# LoraLCD.net
KiCad netlist of a schematic drawn in EAGLE
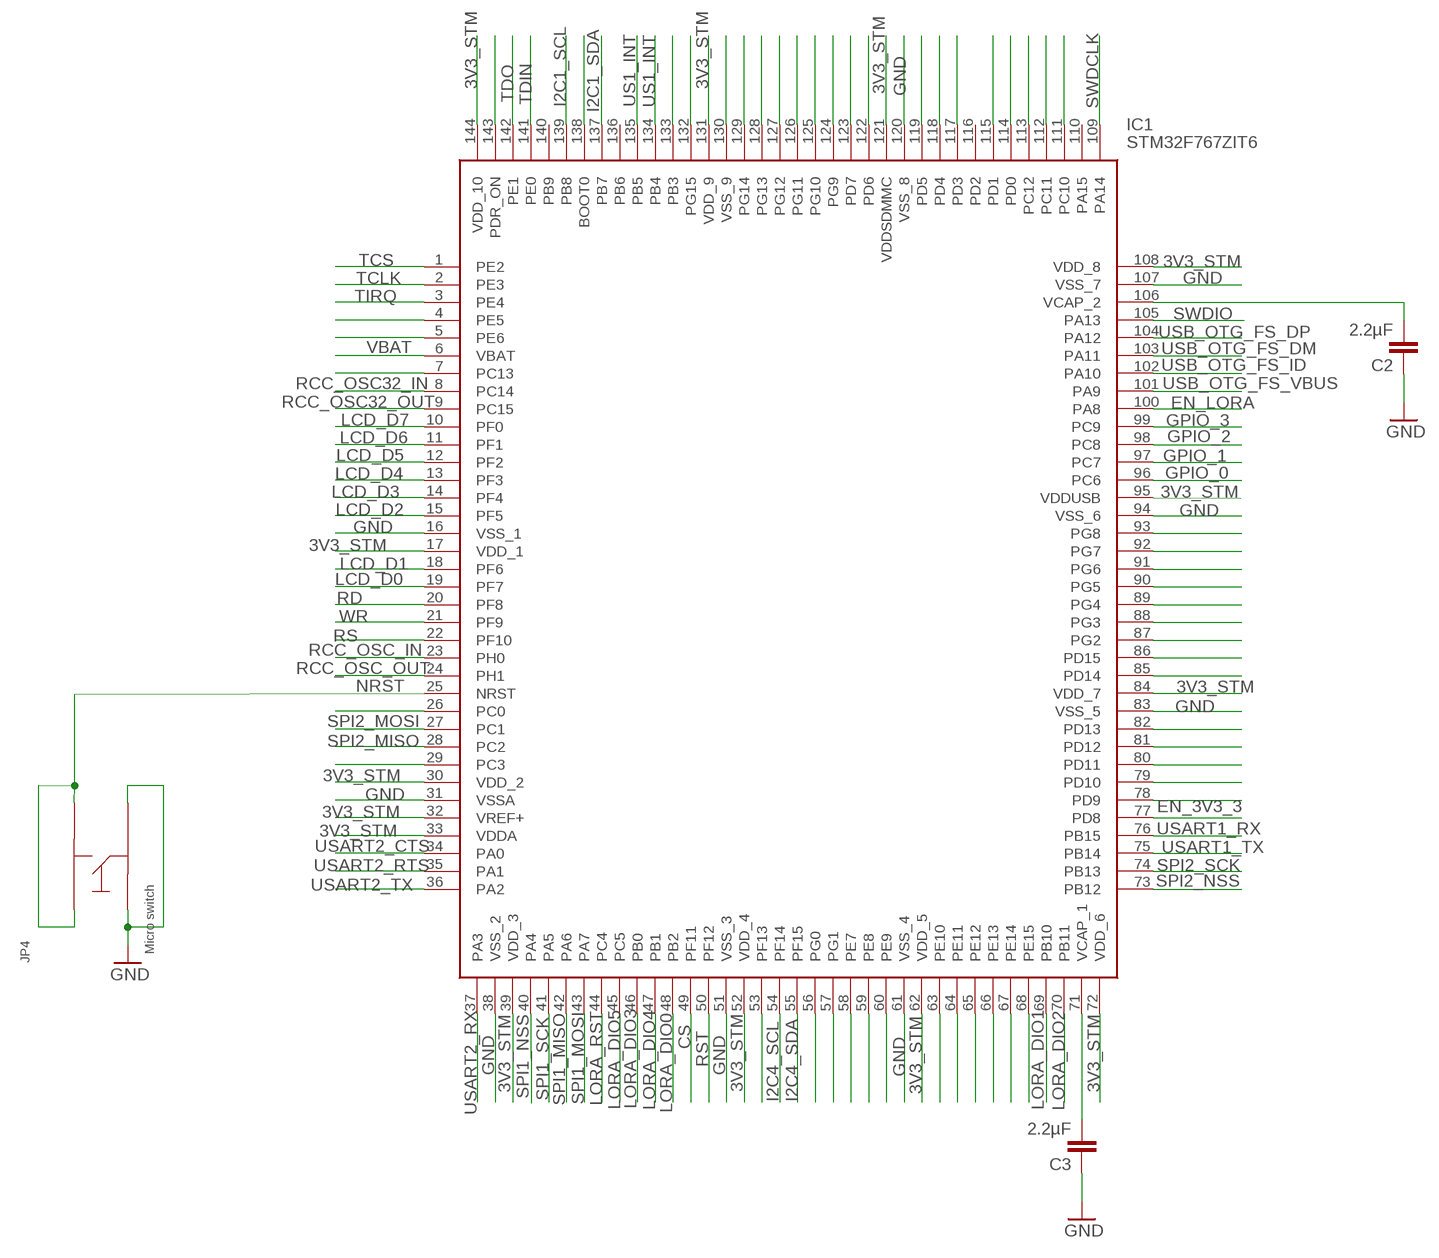
[diagram p0: schematic, sheet 1]
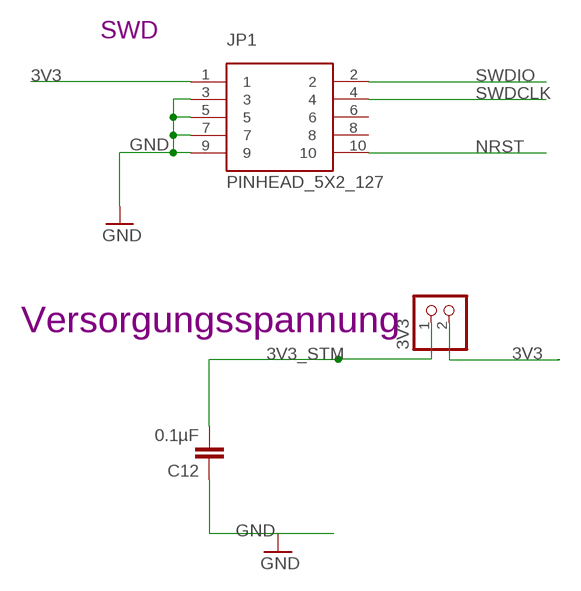
[diagram p1: schematic, sheet 2]
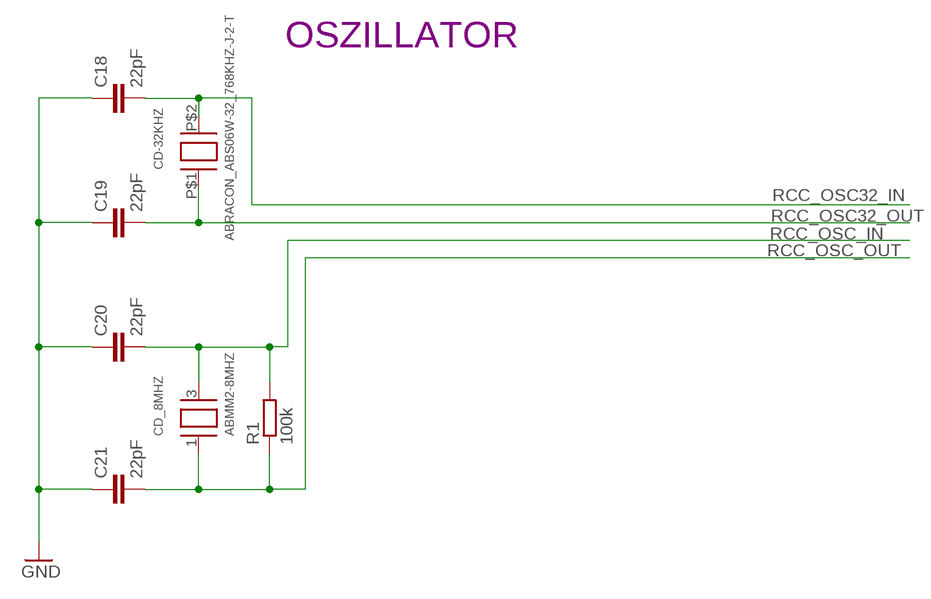
[diagram p2: schematic, sheet 3]
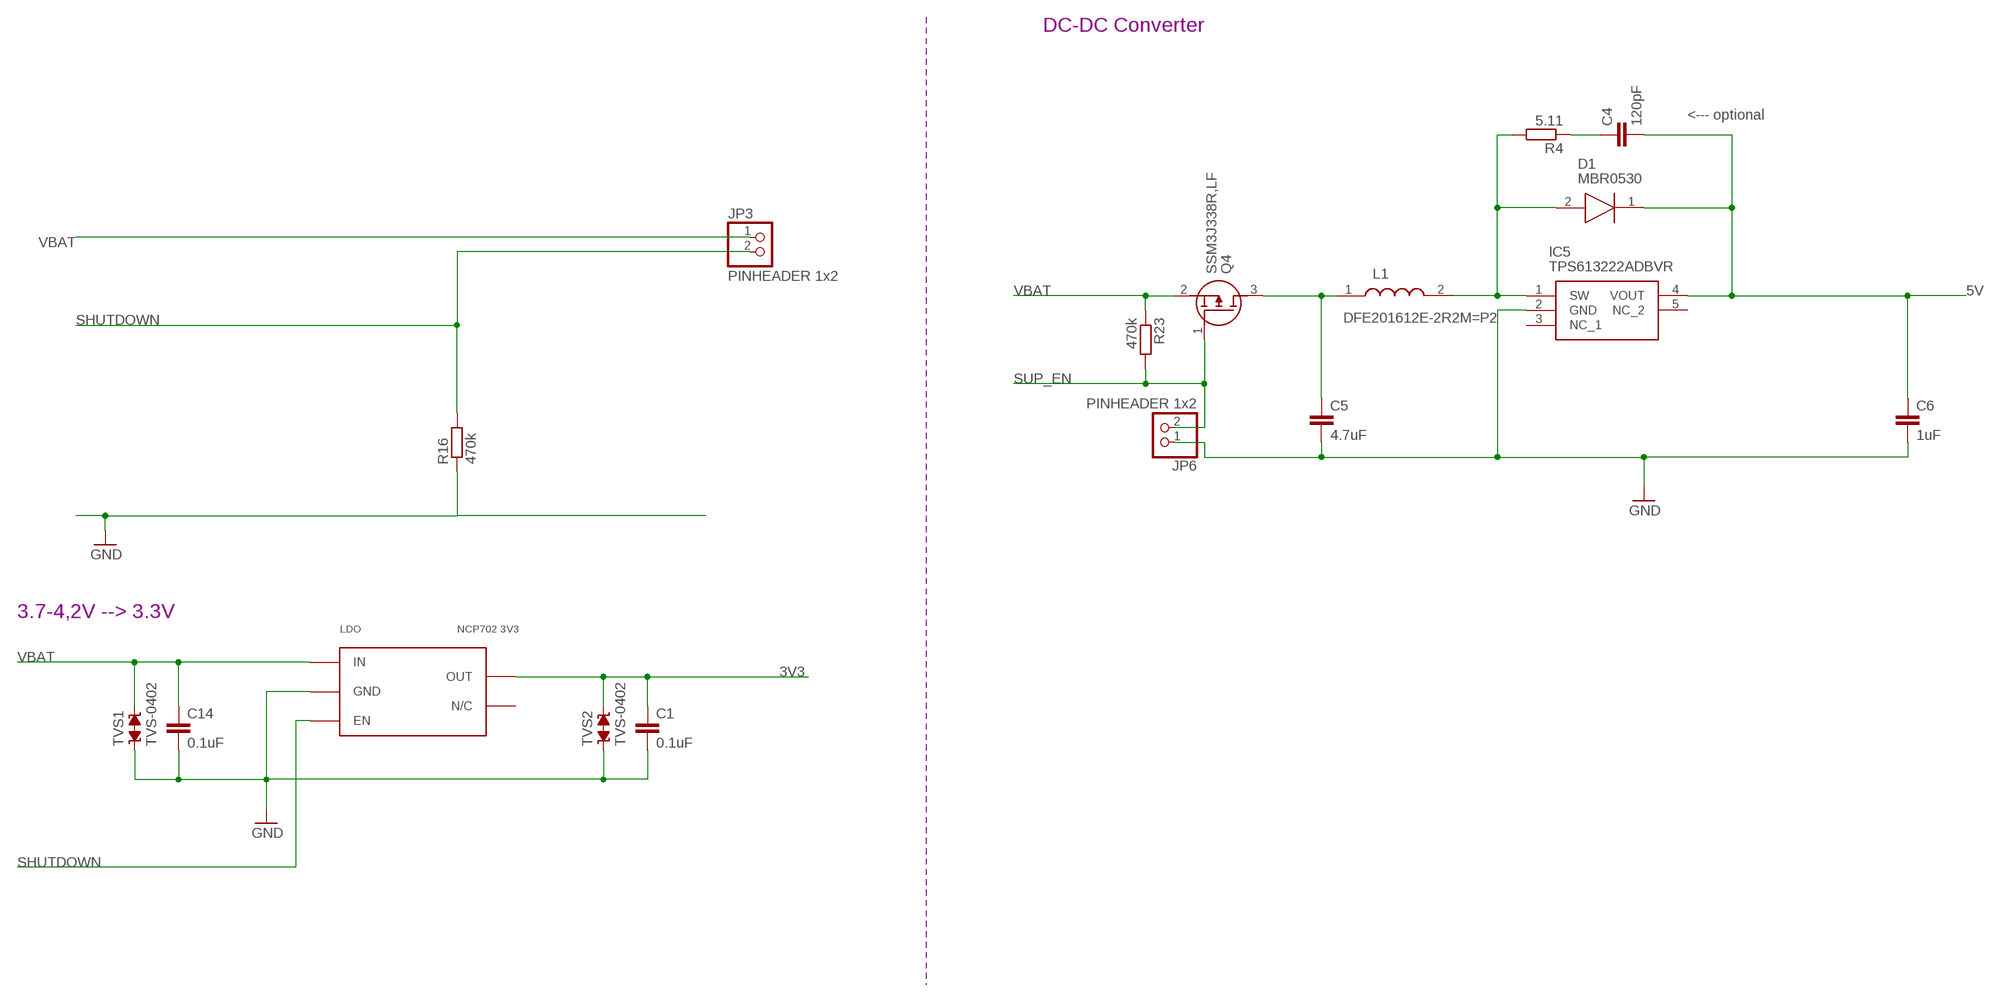
[diagram p3: schematic, sheet 4]
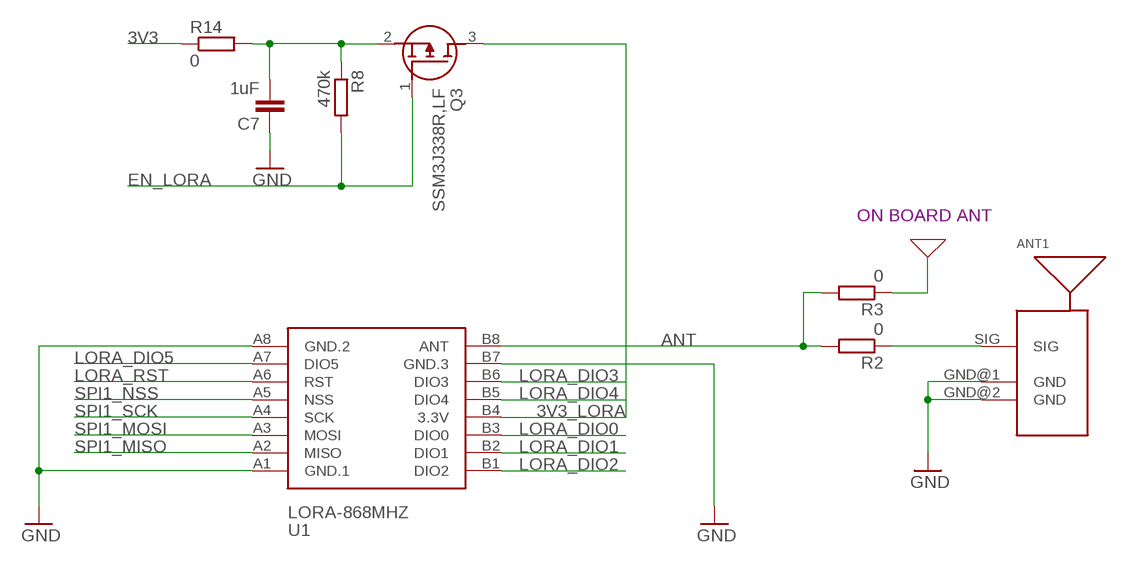
[diagram p4: schematic, sheet 5]
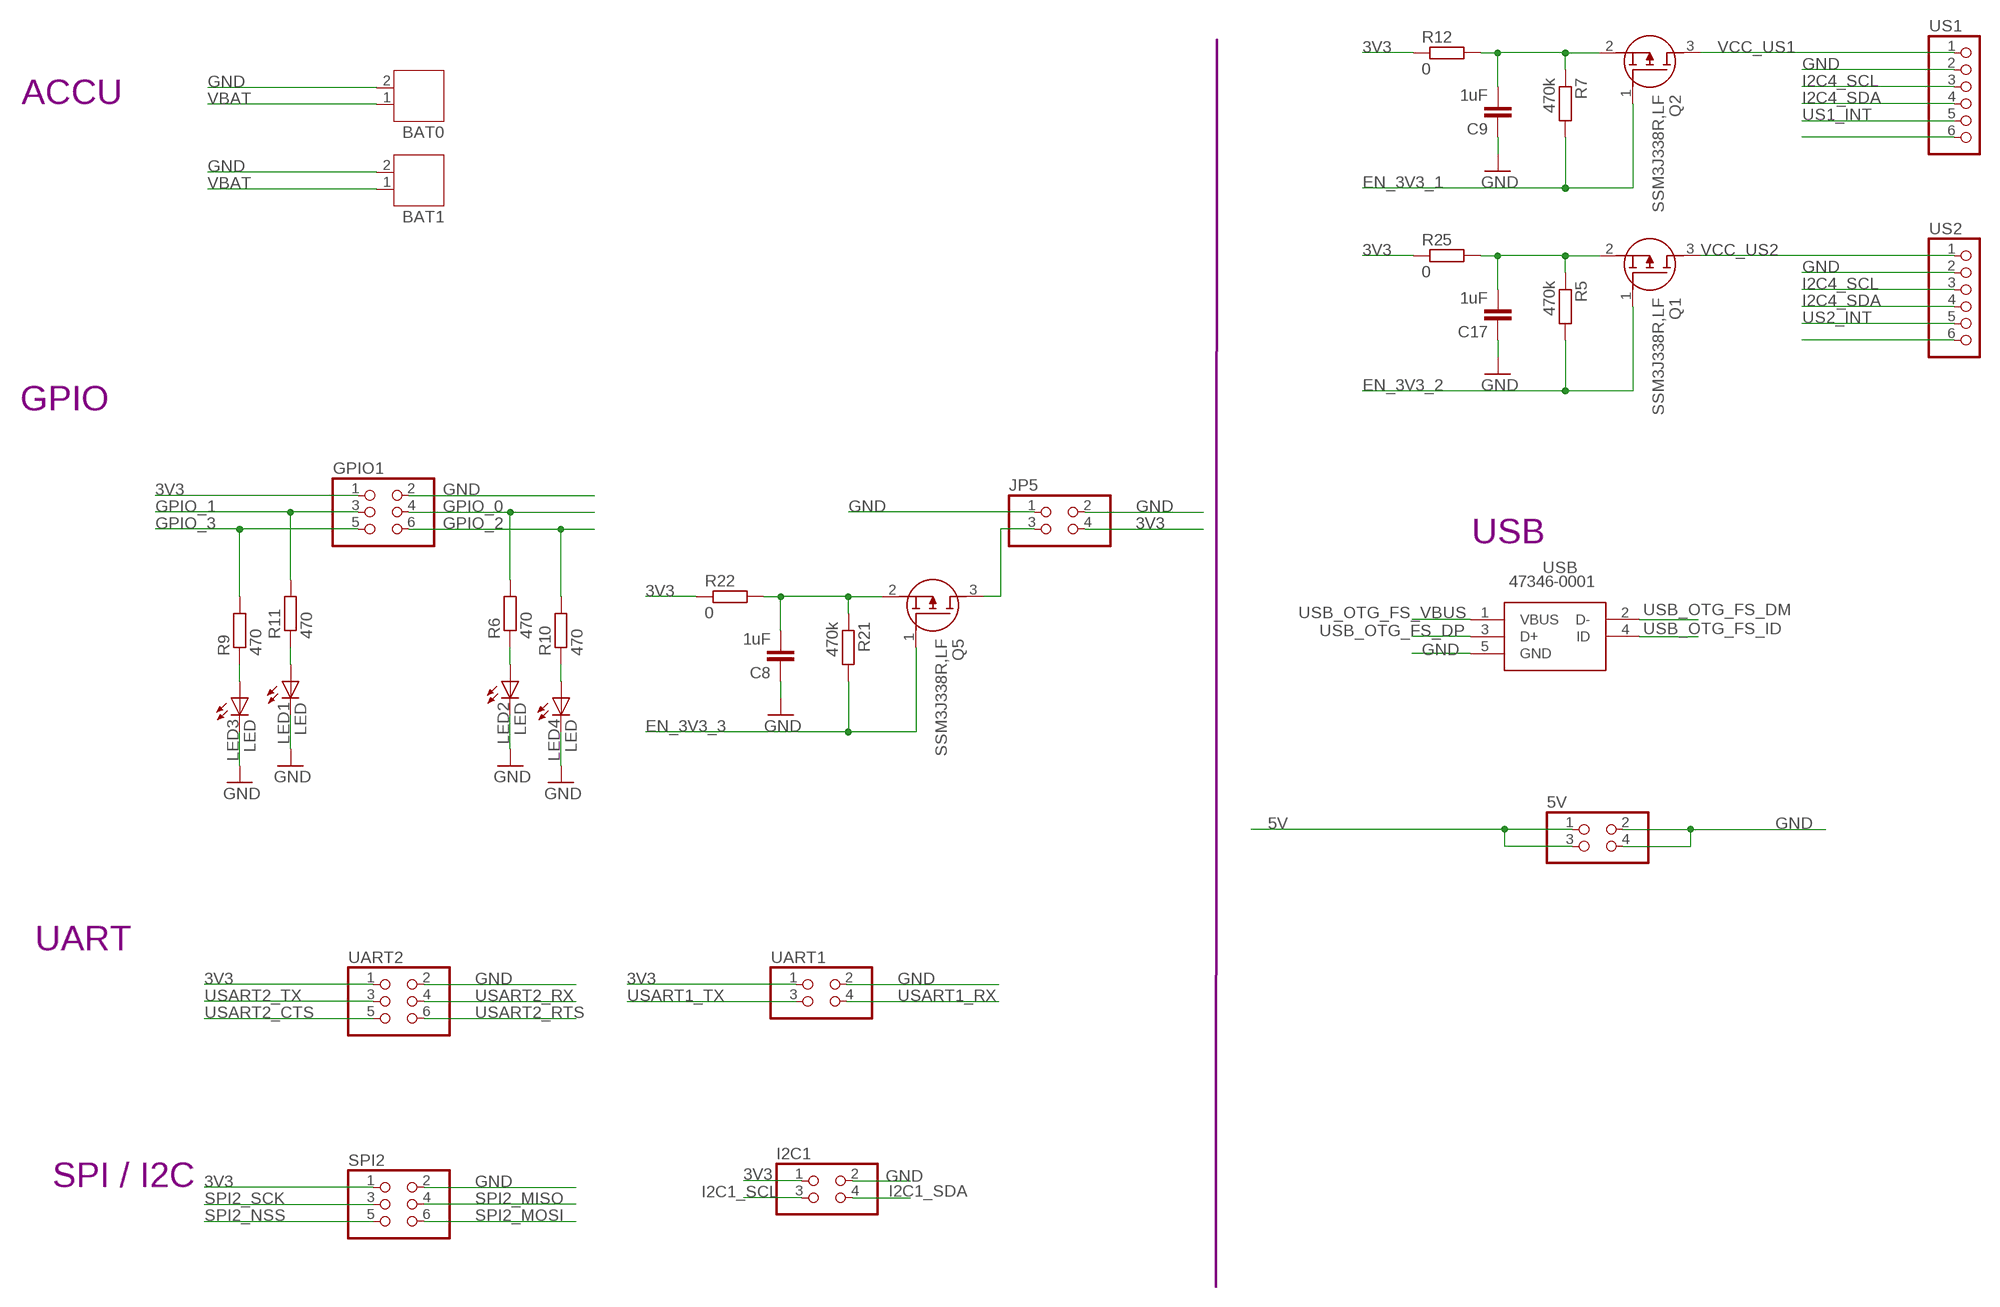
[diagram p5: schematic, sheet 6]
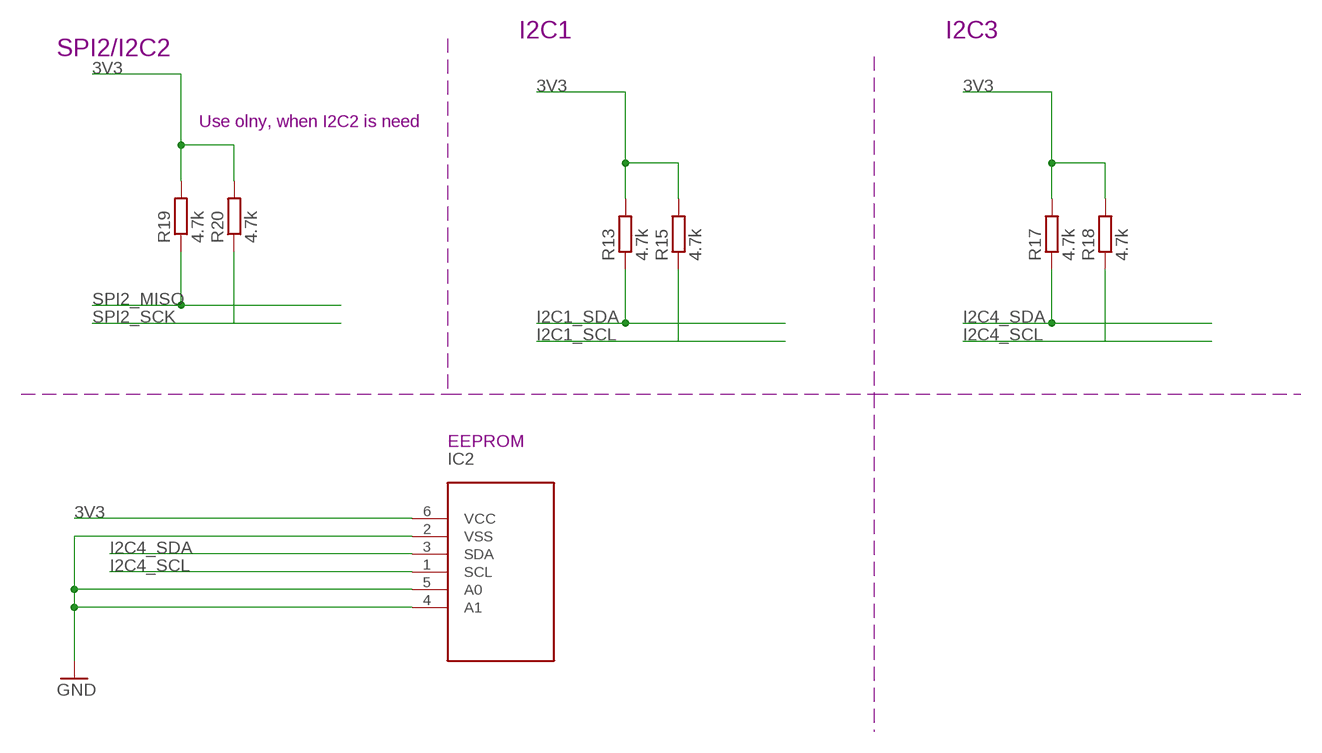
[diagram p6: schematic, sheet 7]
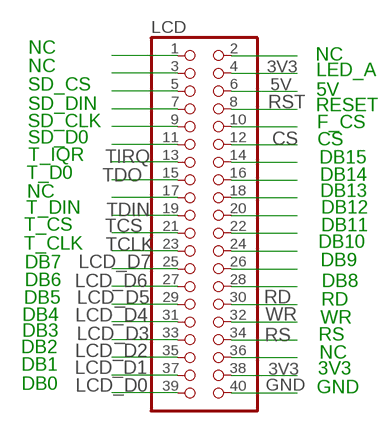
[diagram p7: schematic, sheet 8]

(export (version "E")
  (design (tool "Eeschema 10.0.6"))
  (components
    (comp (ref "C2")
      (value "2.2µF")
      (footprint "eagle-import:C0402K")
      (libsource (lib "eagle-import") (part "C-EUC0402K"))
    )
    (comp (ref "C3")
      (value "2.2µF")
      (footprint "eagle-import:C0402K")
      (libsource (lib "eagle-import") (part "C-EUC0402K"))
    )
    (comp (ref "IC1")
      (value "STM32F767ZIT6")
      (footprint "eagle-import:QFP50P2200X2200X160-144N")
      (fields (field (name "MOUSER_PART_NUMBER") "511-STM32F767ZIT6"))
      (libsource (lib "eagle-import") (part "STM32F767ZIT6"))
    )
    (comp (ref "JP4")
      (value "MICRO_SWITCH_6MM")
      (footprint "eagle-import:SKQGADE010")
      (fields
        (field (name "MPN") "SKQGABE010")
        (field (name "MF") "ALPS")
        (field (name "MPN_1") "SKQGADE010")
      )
      (libsource (lib "eagle-import") (part "MICRO_SWITCH_6MM"))
    )
    (comp (ref "IC2")
      (value "24AA025E64T-I/OT")
      (footprint "eagle-import:SOT23-6")
      (fields (field (name "MF") "Microchip Technology"))
      (libsource (lib "eagle-import") (part "24AA025E48T-I/OT"))
    )
    (comp (ref "R13")
      (value "4.7k")
      (footprint "eagle-import:C0402K")
      (libsource (lib "eagle-import") (part "R_0402WEB_0402"))
    )
    (comp (ref "R15")
      (value "4.7k")
      (footprint "eagle-import:C0402K")
      (libsource (lib "eagle-import") (part "R_0402WEB_0402"))
    )
    (comp (ref "R17")
      (value "4.7k")
      (footprint "eagle-import:C0402K")
      (libsource (lib "eagle-import") (part "R_0402WEB_0402"))
    )
    (comp (ref "R18")
      (value "4.7k")
      (footprint "eagle-import:C0402K")
      (libsource (lib "eagle-import") (part "R_0402WEB_0402"))
    )
    (comp (ref "R19")
      (value "4.7k")
      (footprint "eagle-import:C0402K")
      (libsource (lib "eagle-import") (part "R_0402WEB_0402"))
    )
    (comp (ref "R20")
      (value "4.7k")
      (footprint "eagle-import:C0402K")
      (libsource (lib "eagle-import") (part "R_0402WEB_0402"))
    )
    (comp (ref "C18")
      (value "22pF")
      (footprint "eagle-import:C0402K")
      (libsource (lib "eagle-import") (part "C-EUC0402K"))
    )
    (comp (ref "C19")
      (value "22pF")
      (footprint "eagle-import:C0402K")
      (libsource (lib "eagle-import") (part "C-EUC0402K"))
    )
    (comp (ref "C20")
      (value "22pF")
      (footprint "eagle-import:C0402K")
      (libsource (lib "eagle-import") (part "C-EUC0402K"))
    )
    (comp (ref "C21")
      (value "22pF")
      (footprint "eagle-import:C0402K")
      (libsource (lib "eagle-import") (part "C-EUC0402K"))
    )
    (comp (ref "CD-32KHZ")
      (value "ABRACON_ABS06W-32_768KHZ-J-2-T")
      (footprint "eagle-import:2MM_X_1_2MM")
      (libsource (lib "eagle-import") (part "ABRACON_ABS06W-32_768KHZ-J-2-T"))
    )
    (comp (ref "CD_8MHZ")
      (value "ABMM2-8MHZ")
      (footprint "eagle-import:CRYSTAL_ABRACON_6MM_3.6MM")
      (fields (field (name "MPN") "ABMM2-8.0000MHZ-E1-T"))
      (libsource (lib "eagle-import") (part "ABMM2-8MHZ"))
    )
    (comp (ref "R1")
      (value "100k")
      (footprint "eagle-import:C0402K")
      (libsource (lib "eagle-import") (part "R_0402WEB_0402"))
    )
    (comp (ref "ANT1")
      (value "U.FL-R-SMT-1")
      (footprint "eagle-import:UFL_HIROSE")
      (fields (field (name "MF") "HIROSE Connector") (field (name "MPN") "U.FL-R-SMT-1(10)"))
      (libsource (lib "eagle-import") (part "U.FL-R-SMT-1"))
    )
    (comp (ref "C7")
      (value "1uF")
      (footprint "eagle-import:C0402K")
      (libsource (lib "eagle-import") (part "C-EUC0402K"))
    )
    (comp (ref "Q3")
      (value "SSM3J338R,LF")
      (footprint "eagle-import:SSM3J332RLFT")
      (fields (field (name "MOUSER_PART_NUMBER") "757-SSM3J338RLF"))
      (libsource (lib "eagle-import") (part "SSM3J338R,LF"))
    )
    (comp (ref "R2")
      (value "0")
      (footprint "eagle-import:C0402K")
      (libsource (lib "eagle-import") (part "R_0402WEB_0402"))
    )
    (comp (ref "R3")
      (value "0")
      (footprint "eagle-import:C0402K")
      (libsource (lib "eagle-import") (part "R_0402WEB_0402"))
    )
    (comp (ref "R8")
      (value "470k")
      (footprint "eagle-import:R0402")
      (libsource (lib "eagle-import") (part "R-EU_R0402"))
    )
    (comp (ref "R14")
      (value "0")
      (footprint "eagle-import:R0402")
      (libsource (lib "eagle-import") (part "R-EU_R0402"))
    )
    (comp (ref "U1")
      (value "LORA-868MHZ")
      (footprint "eagle-import:WIRELESS-LORA-RFM95W#SMD")
      (libsource (lib "eagle-import") (part "WIRELESS-LORA-RFM95W#SMD"))
    )
    (comp (ref "3V3")
      (value "PINHD-1X2")
      (footprint "eagle-import:1X02")
      (libsource (lib "eagle-import") (part "PINHD-1X2"))
    )
    (comp (ref "C12")
      (value "0.1µF")
      (footprint "eagle-import:C0402K")
      (libsource (lib "eagle-import") (part "C-EUC0402K"))
    )
    (comp (ref "JP1")
      (value "PINHEAD_5X2_127")
      (footprint "eagle-import:PINHEAD_2X5_127")
      (fields (field (name "MPN") "3221-10-0100-00"))
      (libsource (lib "eagle-import") (part "PINHEAD_5X2_127"))
    )
    (comp (ref "C1")
      (value "0.1uF")
      (footprint "eagle-import:C0402K")
      (fields (field (name "MF") "NOVA") (field (name "MPN") "CCC-23"))
      (libsource (lib "eagle-import") (part "C-EUC0402K"))
    )
    (comp (ref "C4")
      (value "120pF")
      (footprint "eagle-import:C0402K")
      (fields (field (name "MPN") "GRM1555C1H121JA01D"))
      (libsource (lib "eagle-import") (part "C-EUC0402K"))
    )
    (comp (ref "C5")
      (value "4.7uF")
      (footprint "eagle-import:C0603K")
      (fields (field (name "MF") "Taiyo Yuden") (field (name "MPN") "JMK107BB7475KA-T "))
      (libsource (lib "eagle-import") (part "C-EUC0603K"))
    )
    (comp (ref "C6")
      (value "1uF")
      (footprint "eagle-import:C0603K")
      (libsource (lib "eagle-import") (part "C-EUC0603K"))
    )
    (comp (ref "C14")
      (value "0.1uF")
      (footprint "eagle-import:C0402K")
      (libsource (lib "eagle-import") (part "C-EUC0402K"))
    )
    (comp (ref "D1")
      (value "MBR0530")
      (footprint "eagle-import:SOD3716X135N")
      (fields (field (name "MOUSER_PART_NUMBER") "512-MBR0530"))
      (libsource (lib "eagle-import") (part "MBR0530"))
    )
    (comp (ref "IC5")
      (value "TPS613222ADBVR")
      (footprint "eagle-import:SOT95P280X145-5N")
      (fields (field (name "MOUSER_PART_NUMBER") "595-TPS613222ADBVR"))
      (libsource (lib "eagle-import") (part "TPS613222ADBVR"))
    )
    (comp (ref "JP3")
      (value "PINHEADER 1x2")
      (footprint "eagle-import:1X02")
      (libsource (lib "eagle-import") (part "PINHD-1X2"))
    )
    (comp (ref "JP6")
      (value "PINHEADER 1x2")
      (footprint "eagle-import:1X02")
      (libsource (lib "eagle-import") (part "PINHD-1X2"))
    )
    (comp (ref "L1")
      (value "DFE201612E-2R2M=P2")
      (footprint "eagle-import:INDC2016X120N")
      (fields (field (name "MOUSER_PART_NUMBER") "81-DFE201612E-2R2MP2"))
      (libsource (lib "eagle-import") (part "DFE201612E-2R2M=P2"))
    )
    (comp (ref "LDO")
      (value "NCP702 3V3")
      (footprint "eagle-import:SOT563")
      (fields
        (field (name "MOUSER_PART_NUMBER") "863-NCP702SN33T1G")
        (field (name "MF") "ON Semiconductor")
        (field (name "MPN") "NCP702SN33T1G")
      )
      (libsource (lib "eagle-import") (part "NCP702"))
    )
    (comp (ref "Q4")
      (value "SSM3J338R,LF")
      (footprint "eagle-import:SSM3J332RLFT")
      (fields (field (name "MOUSER_PART_NUMBER") "757-SSM3J338RLF"))
      (libsource (lib "eagle-import") (part "SSM3J338R,LF"))
    )
    (comp (ref "R4")
      (value "5.11")
      (footprint "eagle-import:R0402")
      (fields (field (name "MF") "Yageo") (field (name "MPN") "RC0402FR-132M2L "))
      (libsource (lib "eagle-import") (part "R-EU_R0402"))
    )
    (comp (ref "R16")
      (value "470k")
      (footprint "eagle-import:R0402")
      (libsource (lib "eagle-import") (part "R-EU_R0402"))
    )
    (comp (ref "R23")
      (value "470k")
      (footprint "eagle-import:R0402")
      (libsource (lib "eagle-import") (part "R-EU_R0402"))
    )
    (comp (ref "TVS1")
      (value "TVS-0402")
      (footprint "eagle-import:TVS0402")
      (fields
        (field (name "MPN") "GG0402050R3C2P")
        (field (name "MF") "Littelfuse")
        (field (name "MPN_1") "PESD0402-140 ")
      )
      (libsource (lib "eagle-import") (part "TVS-0402"))
    )
    (comp (ref "TVS2")
      (value "TVS-0402")
      (footprint "eagle-import:TVS0402")
      (fields
        (field (name "MPN") "GG0402050R3C2P")
        (field (name "MF") "Littelfuse")
        (field (name "MPN_1") "PESD0402-140 ")
      )
      (libsource (lib "eagle-import") (part "TVS-0402"))
    )
    (comp (ref "LCD")
      (value "PINHD-2X20")
      (footprint "eagle-import:2X20")
      (libsource (lib "eagle-import") (part "PINHD-2X20"))
    )
    (comp (ref "5V")
      (value "PINHD-2X2")
      (footprint "eagle-import:2X02")
      (libsource (lib "eagle-import") (part "PINHD-2X2"))
    )
    (comp (ref "BAT0")
      (value "JST-PH2")
      (footprint "eagle-import:JST-PH2")
      (fields (field (name "MF") "JST Sales America Inc.") (field (name "MPN") "B2B-PH-K-S"))
      (libsource (lib "eagle-import") (part "JST-PH2"))
    )
    (comp (ref "BAT1")
      (value "JST-PH2")
      (footprint "eagle-import:JST-PH2")
      (fields (field (name "MF") "JST Sales America Inc.") (field (name "MPN") "B2B-PH-K-S"))
      (libsource (lib "eagle-import") (part "JST-PH2"))
    )
    (comp (ref "C8")
      (value "1uF")
      (footprint "eagle-import:C0402K")
      (libsource (lib "eagle-import") (part "C-EUC0402K"))
    )
    (comp (ref "C9")
      (value "1uF")
      (footprint "eagle-import:C0402K")
      (libsource (lib "eagle-import") (part "C-EUC0402K"))
    )
    (comp (ref "C17")
      (value "1uF")
      (footprint "eagle-import:C0402K")
      (libsource (lib "eagle-import") (part "C-EUC0402K"))
    )
    (comp (ref "GPIO1")
      (value "PINHD-2X3")
      (footprint "eagle-import:2X03")
      (libsource (lib "eagle-import") (part "PINHD-2X3"))
    )
    (comp (ref "I2C1")
      (value "PINHD-2X2")
      (footprint "eagle-import:2X02")
      (libsource (lib "eagle-import") (part "PINHD-2X2"))
    )
    (comp (ref "JP5")
      (value "PINHD-2X2")
      (footprint "eagle-import:2X02")
      (libsource (lib "eagle-import") (part "PINHD-2X2"))
    )
    (comp (ref "LED1")
      (value "LED")
      (footprint "eagle-import:0603_AK")
      (fields (field (name "MPN") "LB Q39G-L2OO-35-1"))
      (libsource (lib "eagle-import") (part "LED"))
    )
    (comp (ref "LED2")
      (value "LED")
      (footprint "eagle-import:0603_AK")
      (fields (field (name "MPN") "LB Q39G-L2OO-35-1"))
      (libsource (lib "eagle-import") (part "LED"))
    )
    (comp (ref "LED3")
      (value "LED")
      (footprint "eagle-import:0603_AK")
      (fields (field (name "MPN") "LB Q39G-L2OO-35-1"))
      (libsource (lib "eagle-import") (part "LED"))
    )
    (comp (ref "LED4")
      (value "LED")
      (footprint "eagle-import:0603_AK")
      (fields (field (name "MPN") "LB Q39G-L2OO-35-1"))
      (libsource (lib "eagle-import") (part "LED"))
    )
    (comp (ref "Q1")
      (value "SSM3J338R,LF")
      (footprint "eagle-import:SSM3J332RLFT")
      (fields (field (name "MOUSER_PART_NUMBER") "757-SSM3J338RLF"))
      (libsource (lib "eagle-import") (part "SSM3J338R,LF"))
    )
    (comp (ref "Q2")
      (value "SSM3J338R,LF")
      (footprint "eagle-import:SSM3J332RLFT")
      (fields (field (name "MOUSER_PART_NUMBER") "757-SSM3J338RLF"))
      (libsource (lib "eagle-import") (part "SSM3J338R,LF"))
    )
    (comp (ref "Q5")
      (value "SSM3J338R,LF")
      (footprint "eagle-import:SSM3J332RLFT")
      (fields (field (name "MOUSER_PART_NUMBER") "757-SSM3J338RLF"))
      (libsource (lib "eagle-import") (part "SSM3J338R,LF"))
    )
    (comp (ref "R5")
      (value "470k")
      (footprint "eagle-import:R0402")
      (libsource (lib "eagle-import") (part "R-EU_R0402"))
    )
    (comp (ref "R6")
      (value "470")
      (footprint "eagle-import:R0402")
      (libsource (lib "eagle-import") (part "R-EU_R0402"))
    )
    (comp (ref "R7")
      (value "470k")
      (footprint "eagle-import:R0402")
      (libsource (lib "eagle-import") (part "R-EU_R0402"))
    )
    (comp (ref "R9")
      (value "470")
      (footprint "eagle-import:R0402")
      (libsource (lib "eagle-import") (part "R-EU_R0402"))
    )
    (comp (ref "R10")
      (value "470")
      (footprint "eagle-import:R0402")
      (libsource (lib "eagle-import") (part "R-EU_R0402"))
    )
    (comp (ref "R11")
      (value "470")
      (footprint "eagle-import:R0402")
      (libsource (lib "eagle-import") (part "R-EU_R0402"))
    )
    (comp (ref "R12")
      (value "0")
      (footprint "eagle-import:R0402")
      (libsource (lib "eagle-import") (part "R-EU_R0402"))
    )
    (comp (ref "R21")
      (value "470k")
      (footprint "eagle-import:R0402")
      (libsource (lib "eagle-import") (part "R-EU_R0402"))
    )
    (comp (ref "R22")
      (value "0")
      (footprint "eagle-import:R0402")
      (libsource (lib "eagle-import") (part "R-EU_R0402"))
    )
    (comp (ref "R25")
      (value "0")
      (footprint "eagle-import:R0402")
      (libsource (lib "eagle-import") (part "R-EU_R0402"))
    )
    (comp (ref "SPI2")
      (value "PINHD-2X3")
      (footprint "eagle-import:2X03")
      (libsource (lib "eagle-import") (part "PINHD-2X3"))
    )
    (comp (ref "UART1")
      (value "PINHD-2X2")
      (footprint "eagle-import:2X02")
      (libsource (lib "eagle-import") (part "PINHD-2X2"))
    )
    (comp (ref "UART2")
      (value "PINHD-2X3")
      (footprint "eagle-import:2X03")
      (libsource (lib "eagle-import") (part "PINHD-2X3"))
    )
    (comp (ref "US1")
      (value "PINHD-1X6")
      (footprint "eagle-import:1X06")
      (libsource (lib "eagle-import") (part "PINHD-1X6"))
    )
    (comp (ref "US2")
      (value "PINHD-1X6")
      (footprint "eagle-import:1X06")
      (libsource (lib "eagle-import") (part "PINHD-1X6"))
    )
    (comp (ref "USB")
      (value "47346-0001")
      (footprint "eagle-import:47346-0001")
      (libsource (lib "eagle-import") (part "47346-0001"))
    )
  )
  (nets
    (net (code "1") (name "3V3") (class "Default")
      (node (ref "3V3") (pin "2") (pinfunction "2_2") (pintype "passive"))
      (node (ref "C1") (pin "1") (pinfunction "1_1") (pintype "passive"))
      (node (ref "GPIO1") (pin "1") (pinfunction "1_1") (pintype "passive"))
      (node (ref "I2C1") (pin "1") (pinfunction "1_1") (pintype "passive"))
      (node (ref "IC2") (pin "6") (pinfunction "VCC_6") (pintype "bidirectional"))
      (node (ref "JP1") (pin "1") (pinfunction "1_1") (pintype "bidirectional"))
      (node (ref "JP5") (pin "4") (pinfunction "4_4") (pintype "passive"))
      (node (ref "LCD") (pin "38") (pinfunction "38_38") (pintype "passive"))
      (node (ref "LCD") (pin "4") (pinfunction "4_4") (pintype "passive"))
      (node (ref "LDO") (pin "P$5") (pinfunction "OUT_P$5") (pintype "bidirectional"))
      (node (ref "R12") (pin "1") (pinfunction "1_1") (pintype "passive"))
      (node (ref "R13") (pin "2") (pinfunction "2_2") (pintype "passive"))
      (node (ref "R14") (pin "1") (pinfunction "1_1") (pintype "passive"))
      (node (ref "R15") (pin "2") (pinfunction "2_2") (pintype "passive"))
      (node (ref "R17") (pin "2") (pinfunction "2_2") (pintype "passive"))
      (node (ref "R18") (pin "2") (pinfunction "2_2") (pintype "passive"))
      (node (ref "R19") (pin "2") (pinfunction "2_2") (pintype "passive"))
      (node (ref "R20") (pin "2") (pinfunction "2_2") (pintype "passive"))
      (node (ref "R22") (pin "1") (pinfunction "1_1") (pintype "passive"))
      (node (ref "R25") (pin "1") (pinfunction "1_1") (pintype "passive"))
      (node (ref "SPI2") (pin "1") (pinfunction "1_1") (pintype "passive"))
      (node (ref "TVS2") (pin "2") (pinfunction "2_2") (pintype "passive"))
      (node (ref "UART1") (pin "1") (pinfunction "1_1") (pintype "passive"))
      (node (ref "UART2") (pin "1") (pinfunction "1_1") (pintype "passive"))
    )
    (net (code "2") (name "3V3_LORA") (class "Default")
      (node (ref "Q3") (pin "3") (pinfunction "D_3") (pintype "bidirectional"))
      (node (ref "U1") (pin "B4") (pinfunction "3.3V_B4") (pintype "power_in"))
    )
    (net (code "3") (name "3V3_STM") (class "Default")
      (node (ref "3V3") (pin "1") (pinfunction "1_1") (pintype "passive"))
      (node (ref "C12") (pin "2") (pinfunction "2_2") (pintype "passive"))
      (node (ref "IC1") (pin "108") (pinfunction "VDD_8_108") (pintype "bidirectional"))
      (node (ref "IC1") (pin "121") (pinfunction "VDDSDMMC_121") (pintype "bidirectional"))
      (node (ref "IC1") (pin "131") (pinfunction "VDD_9_131") (pintype "bidirectional"))
      (node (ref "IC1") (pin "144") (pinfunction "VDD_10_144") (pintype "bidirectional"))
      (node (ref "IC1") (pin "17") (pinfunction "VDD_1_17") (pintype "bidirectional"))
      (node (ref "IC1") (pin "30") (pinfunction "VDD_2_30") (pintype "bidirectional"))
      (node (ref "IC1") (pin "32") (pinfunction "VREF+_32") (pintype "bidirectional"))
      (node (ref "IC1") (pin "33") (pinfunction "VDDA_33") (pintype "bidirectional"))
      (node (ref "IC1") (pin "39") (pinfunction "VDD_3_39") (pintype "bidirectional"))
      (node (ref "IC1") (pin "52") (pinfunction "VDD_4_52") (pintype "bidirectional"))
      (node (ref "IC1") (pin "62") (pinfunction "VDD_5_62") (pintype "bidirectional"))
      (node (ref "IC1") (pin "72") (pinfunction "VDD_6_72") (pintype "bidirectional"))
      (node (ref "IC1") (pin "84") (pinfunction "VDD_7_84") (pintype "bidirectional"))
      (node (ref "IC1") (pin "95") (pinfunction "VDDUSB_95") (pintype "bidirectional"))
    )
    (net (code "4") (name "5V") (class "Default")
      (node (ref "5V") (pin "1") (pinfunction "1_1") (pintype "passive"))
      (node (ref "5V") (pin "3") (pinfunction "3_3") (pintype "passive"))
      (node (ref "C4") (pin "2") (pinfunction "2_2") (pintype "passive"))
      (node (ref "C6") (pin "1") (pinfunction "1_1") (pintype "passive"))
      (node (ref "D1") (pin "1") (pinfunction "K_1") (pintype "bidirectional"))
      (node (ref "IC5") (pin "4") (pinfunction "VOUT_4") (pintype "bidirectional"))
      (node (ref "LCD") (pin "6") (pinfunction "6_6") (pintype "passive"))
    )
    (net (code "5") (name "ANT") (class "Default")
      (node (ref "R2") (pin "2") (pinfunction "2_2") (pintype "passive"))
      (node (ref "R3") (pin "2") (pinfunction "2_2") (pintype "passive"))
      (node (ref "U1") (pin "B8") (pinfunction "ANT_B8") (pintype "passive"))
    )
    (net (code "6") (name "CS") (class "Default")
      (node (ref "IC1") (pin "49") (pinfunction "PF11_49") (pintype "bidirectional"))
      (node (ref "LCD") (pin "12") (pinfunction "12_12") (pintype "passive"))
    )
    (net (code "7") (name "EN_3V3_1") (class "Default")
      (node (ref "Q2") (pin "1") (pinfunction "G_1") (pintype "bidirectional"))
      (node (ref "R7") (pin "2") (pinfunction "2_2") (pintype "passive"))
    )
    (net (code "8") (name "EN_3V3_2") (class "Default")
      (node (ref "Q1") (pin "1") (pinfunction "G_1") (pintype "bidirectional"))
      (node (ref "R5") (pin "2") (pinfunction "2_2") (pintype "passive"))
    )
    (net (code "9") (name "EN_3V3_3") (class "Default")
      (node (ref "IC1") (pin "77") (pinfunction "PD8_77") (pintype "bidirectional"))
      (node (ref "Q5") (pin "1") (pinfunction "G_1") (pintype "bidirectional"))
      (node (ref "R21") (pin "2") (pinfunction "2_2") (pintype "passive"))
    )
    (net (code "10") (name "EN_LORA") (class "Default")
      (node (ref "IC1") (pin "100") (pinfunction "PA8_100") (pintype "bidirectional"))
      (node (ref "Q3") (pin "1") (pinfunction "G_1") (pintype "bidirectional"))
      (node (ref "R8") (pin "2") (pinfunction "2_2") (pintype "passive"))
    )
    (net (code "11") (name "GND") (class "Default")
      (node (ref "5V") (pin "2") (pinfunction "2_2") (pintype "passive"))
      (node (ref "5V") (pin "4") (pinfunction "4_4") (pintype "passive"))
      (node (ref "ANT1") (pin "GND@1") (pinfunction "GND_GND@1") (pintype "bidirectional"))
      (node (ref "ANT1") (pin "GND@2") (pinfunction "GND_GND@2") (pintype "bidirectional"))
      (node (ref "BAT0") (pin "2") (pinfunction "2_2") (pintype "passive"))
      (node (ref "BAT1") (pin "2") (pinfunction "2_2") (pintype "passive"))
      (node (ref "C1") (pin "2") (pinfunction "2_2") (pintype "passive"))
      (node (ref "C12") (pin "1") (pinfunction "1_1") (pintype "passive"))
      (node (ref "C14") (pin "2") (pinfunction "2_2") (pintype "passive"))
      (node (ref "C17") (pin "1") (pinfunction "1_1") (pintype "passive"))
      (node (ref "C18") (pin "1") (pinfunction "1_1") (pintype "passive"))
      (node (ref "C19") (pin "1") (pinfunction "1_1") (pintype "passive"))
      (node (ref "C2") (pin "1") (pinfunction "1_1") (pintype "passive"))
      (node (ref "C20") (pin "1") (pinfunction "1_1") (pintype "passive"))
      (node (ref "C21") (pin "1") (pinfunction "1_1") (pintype "passive"))
      (node (ref "C3") (pin "1") (pinfunction "1_1") (pintype "passive"))
      (node (ref "C5") (pin "2") (pinfunction "2_2") (pintype "passive"))
      (node (ref "C6") (pin "2") (pinfunction "2_2") (pintype "passive"))
      (node (ref "C7") (pin "1") (pinfunction "1_1") (pintype "passive"))
      (node (ref "C8") (pin "1") (pinfunction "1_1") (pintype "passive"))
      (node (ref "C9") (pin "1") (pinfunction "1_1") (pintype "passive"))
      (node (ref "GPIO1") (pin "2") (pinfunction "2_2") (pintype "passive"))
      (node (ref "I2C1") (pin "2") (pinfunction "2_2") (pintype "passive"))
      (node (ref "IC1") (pin "107") (pinfunction "VSS_7_107") (pintype "bidirectional"))
      (node (ref "IC1") (pin "120") (pinfunction "VSS_8_120") (pintype "bidirectional"))
      (node (ref "IC1") (pin "16") (pinfunction "VSS_1_16") (pintype "bidirectional"))
      (node (ref "IC1") (pin "31") (pinfunction "VSSA_31") (pintype "bidirectional"))
      (node (ref "IC1") (pin "38") (pinfunction "VSS_2_38") (pintype "bidirectional"))
      (node (ref "IC1") (pin "51") (pinfunction "VSS_3_51") (pintype "bidirectional"))
      (node (ref "IC1") (pin "61") (pinfunction "VSS_4_61") (pintype "bidirectional"))
      (node (ref "IC1") (pin "83") (pinfunction "VSS_5_83") (pintype "bidirectional"))
      (node (ref "IC1") (pin "94") (pinfunction "VSS_6_94") (pintype "bidirectional"))
      (node (ref "IC2") (pin "2") (pinfunction "VSS_2") (pintype "bidirectional"))
      (node (ref "IC2") (pin "4") (pinfunction "A1_4") (pintype "bidirectional"))
      (node (ref "IC2") (pin "5") (pinfunction "A0_5") (pintype "bidirectional"))
      (node (ref "IC5") (pin "2") (pinfunction "GND_2") (pintype "bidirectional"))
      (node (ref "JP1") (pin "3") (pinfunction "3_3") (pintype "bidirectional"))
      (node (ref "JP1") (pin "5") (pinfunction "5_5") (pintype "bidirectional"))
      (node (ref "JP1") (pin "7") (pinfunction "7_7") (pintype "bidirectional"))
      (node (ref "JP1") (pin "9") (pinfunction "9_9") (pintype "bidirectional"))
      (node (ref "JP4") (pin "P$3") (pinfunction "P$3_P$3") (pintype "bidirectional"))
      (node (ref "JP4") (pin "P$4") (pinfunction "P$4_P$4") (pintype "bidirectional"))
      (node (ref "JP5") (pin "1") (pinfunction "1_1") (pintype "passive"))
      (node (ref "JP5") (pin "2") (pinfunction "2_2") (pintype "passive"))
      (node (ref "JP6") (pin "1") (pinfunction "1_1") (pintype "passive"))
      (node (ref "LCD") (pin "40") (pinfunction "40_40") (pintype "passive"))
      (node (ref "LDO") (pin "P$2") (pinfunction "GND_P$2") (pintype "bidirectional"))
      (node (ref "LED1") (pin "K") (pinfunction "C_K") (pintype "passive"))
      (node (ref "LED2") (pin "K") (pinfunction "C_K") (pintype "passive"))
      (node (ref "LED3") (pin "K") (pinfunction "C_K") (pintype "passive"))
      (node (ref "LED4") (pin "K") (pinfunction "C_K") (pintype "passive"))
      (node (ref "R16") (pin "1") (pinfunction "1_1") (pintype "passive"))
      (node (ref "SPI2") (pin "2") (pinfunction "2_2") (pintype "passive"))
      (node (ref "TVS1") (pin "1") (pinfunction "1_1") (pintype "passive"))
      (node (ref "TVS2") (pin "1") (pinfunction "1_1") (pintype "passive"))
      (node (ref "U1") (pin "A1") (pinfunction "GND.1_A1") (pintype "power_in"))
      (node (ref "U1") (pin "A8") (pinfunction "GND.2_A8") (pintype "power_in"))
      (node (ref "U1") (pin "B7") (pinfunction "GND.3_B7") (pintype "power_in"))
      (node (ref "UART1") (pin "2") (pinfunction "2_2") (pintype "passive"))
      (node (ref "UART2") (pin "2") (pinfunction "2_2") (pintype "passive"))
      (node (ref "US1") (pin "2") (pinfunction "2_2") (pintype "passive"))
      (node (ref "US2") (pin "2") (pinfunction "2_2") (pintype "passive"))
      (node (ref "USB") (pin "5") (pinfunction "GND_5") (pintype "bidirectional"))
    )
    (net (code "12") (name "GPIO_0") (class "Default")
      (node (ref "GPIO1") (pin "4") (pinfunction "4_4") (pintype "passive"))
      (node (ref "IC1") (pin "96") (pinfunction "PC6_96") (pintype "bidirectional"))
      (node (ref "R6") (pin "2") (pinfunction "2_2") (pintype "passive"))
    )
    (net (code "13") (name "GPIO_1") (class "Default")
      (node (ref "GPIO1") (pin "3") (pinfunction "3_3") (pintype "passive"))
      (node (ref "IC1") (pin "97") (pinfunction "PC7_97") (pintype "bidirectional"))
      (node (ref "R11") (pin "2") (pinfunction "2_2") (pintype "passive"))
    )
    (net (code "14") (name "GPIO_2") (class "Default")
      (node (ref "GPIO1") (pin "6") (pinfunction "6_6") (pintype "passive"))
      (node (ref "IC1") (pin "98") (pinfunction "PC8_98") (pintype "bidirectional"))
      (node (ref "R10") (pin "2") (pinfunction "2_2") (pintype "passive"))
    )
    (net (code "15") (name "GPIO_3") (class "Default")
      (node (ref "GPIO1") (pin "5") (pinfunction "5_5") (pintype "passive"))
      (node (ref "IC1") (pin "99") (pinfunction "PC9_99") (pintype "bidirectional"))
      (node (ref "R9") (pin "2") (pinfunction "2_2") (pintype "passive"))
    )
    (net (code "16") (name "I2C1_SCL") (class "Default")
      (node (ref "I2C1") (pin "3") (pinfunction "3_3") (pintype "passive"))
      (node (ref "IC1") (pin "139") (pinfunction "PB8_139") (pintype "bidirectional"))
      (node (ref "R15") (pin "1") (pinfunction "1_1") (pintype "passive"))
    )
    (net (code "17") (name "I2C1_SDA") (class "Default")
      (node (ref "I2C1") (pin "4") (pinfunction "4_4") (pintype "passive"))
      (node (ref "IC1") (pin "137") (pinfunction "PB7_137") (pintype "bidirectional"))
      (node (ref "R13") (pin "1") (pinfunction "1_1") (pintype "passive"))
    )
    (net (code "18") (name "I2C4_SCL") (class "Default")
      (node (ref "IC1") (pin "54") (pinfunction "PF14_54") (pintype "bidirectional"))
      (node (ref "IC2") (pin "1") (pinfunction "SCL_1") (pintype "bidirectional"))
      (node (ref "R18") (pin "1") (pinfunction "1_1") (pintype "passive"))
      (node (ref "US1") (pin "3") (pinfunction "3_3") (pintype "passive"))
      (node (ref "US2") (pin "3") (pinfunction "3_3") (pintype "passive"))
    )
    (net (code "19") (name "I2C4_SDA") (class "Default")
      (node (ref "IC1") (pin "55") (pinfunction "PF15_55") (pintype "bidirectional"))
      (node (ref "IC2") (pin "3") (pinfunction "SDA_3") (pintype "bidirectional"))
      (node (ref "R17") (pin "1") (pinfunction "1_1") (pintype "passive"))
      (node (ref "US1") (pin "4") (pinfunction "4_4") (pintype "passive"))
      (node (ref "US2") (pin "4") (pinfunction "4_4") (pintype "passive"))
    )
    (net (code "20") (name "LCD_D0") (class "Default")
      (node (ref "IC1") (pin "19") (pinfunction "PF7_19") (pintype "bidirectional"))
      (node (ref "LCD") (pin "39") (pinfunction "39_39") (pintype "passive"))
    )
    (net (code "21") (name "LCD_D1") (class "Default")
      (node (ref "IC1") (pin "18") (pinfunction "PF6_18") (pintype "bidirectional"))
      (node (ref "LCD") (pin "37") (pinfunction "37_37") (pintype "passive"))
    )
    (net (code "22") (name "LCD_D2") (class "Default")
      (node (ref "IC1") (pin "15") (pinfunction "PF5_15") (pintype "bidirectional"))
      (node (ref "LCD") (pin "35") (pinfunction "35_35") (pintype "passive"))
    )
    (net (code "23") (name "LCD_D3") (class "Default")
      (node (ref "IC1") (pin "14") (pinfunction "PF4_14") (pintype "bidirectional"))
      (node (ref "LCD") (pin "33") (pinfunction "33_33") (pintype "passive"))
    )
    (net (code "24") (name "LCD_D4") (class "Default")
      (node (ref "IC1") (pin "13") (pinfunction "PF3_13") (pintype "bidirectional"))
      (node (ref "LCD") (pin "31") (pinfunction "31_31") (pintype "passive"))
    )
    (net (code "25") (name "LCD_D5") (class "Default")
      (node (ref "IC1") (pin "12") (pinfunction "PF2_12") (pintype "bidirectional"))
      (node (ref "LCD") (pin "29") (pinfunction "29_29") (pintype "passive"))
    )
    (net (code "26") (name "LCD_D6") (class "Default")
      (node (ref "IC1") (pin "11") (pinfunction "PF1_11") (pintype "bidirectional"))
      (node (ref "LCD") (pin "27") (pinfunction "27_27") (pintype "passive"))
    )
    (net (code "27") (name "LCD_D7") (class "Default")
      (node (ref "IC1") (pin "10") (pinfunction "PF0_10") (pintype "bidirectional"))
      (node (ref "LCD") (pin "25") (pinfunction "25_25") (pintype "passive"))
    )
    (net (code "28") (name "LORA_DIO0") (class "Default")
      (node (ref "IC1") (pin "48") (pinfunction "PB2_48") (pintype "bidirectional"))
      (node (ref "U1") (pin "B3") (pinfunction "DIO0_B3") (pintype "bidirectional"))
    )
    (net (code "29") (name "LORA_DIO1") (class "Default")
      (node (ref "IC1") (pin "69") (pinfunction "PB10_69") (pintype "bidirectional"))
      (node (ref "U1") (pin "B2") (pinfunction "DIO1_B2") (pintype "bidirectional"))
    )
    (net (code "30") (name "LORA_DIO2") (class "Default")
      (node (ref "IC1") (pin "70") (pinfunction "PB11_70") (pintype "bidirectional"))
      (node (ref "U1") (pin "B1") (pinfunction "DIO2_B1") (pintype "bidirectional"))
    )
    (net (code "31") (name "LORA_DIO3") (class "Default")
      (node (ref "IC1") (pin "46") (pinfunction "PB0_46") (pintype "bidirectional"))
      (node (ref "U1") (pin "B6") (pinfunction "DIO3_B6") (pintype "bidirectional"))
    )
    (net (code "32") (name "LORA_DIO4") (class "Default")
      (node (ref "IC1") (pin "47") (pinfunction "PB1_47") (pintype "bidirectional"))
      (node (ref "U1") (pin "B5") (pinfunction "DIO4_B5") (pintype "bidirectional"))
    )
    (net (code "33") (name "LORA_DIO5") (class "Default")
      (node (ref "IC1") (pin "45") (pinfunction "PC5_45") (pintype "bidirectional"))
      (node (ref "U1") (pin "A7") (pinfunction "DIO5_A7") (pintype "bidirectional"))
    )
    (net (code "34") (name "LORA_RST") (class "Default")
      (node (ref "IC1") (pin "44") (pinfunction "PC4_44") (pintype "bidirectional"))
      (node (ref "U1") (pin "A6") (pinfunction "RST_A6") (pintype "bidirectional"))
    )
    (net (code "35") (name "NRST") (class "Default")
      (node (ref "IC1") (pin "25") (pinfunction "NRST_25") (pintype "bidirectional"))
      (node (ref "JP1") (pin "10") (pinfunction "10_10") (pintype "bidirectional"))
      (node (ref "JP4") (pin "P$1") (pinfunction "P$1_P$1") (pintype "bidirectional"))
      (node (ref "JP4") (pin "P$2") (pinfunction "P$2_P$2") (pintype "bidirectional"))
    )
    (net (code "36") (name "Net-(ANT1-PadSIG)") (class "Default")
      (node (ref "ANT1") (pin "SIG") (pinfunction "SIG_SIG") (pintype "bidirectional"))
      (node (ref "R2") (pin "1") (pinfunction "1_1") (pintype "passive"))
    )
    (net (code "37") (name "Net-(C4-Pad1)") (class "Default")
      (node (ref "C4") (pin "1") (pinfunction "1_1") (pintype "passive"))
      (node (ref "R4") (pin "1") (pinfunction "1_1") (pintype "passive"))
    )
    (net (code "38") (name "Net-(D1-A)") (class "Default")
      (node (ref "D1") (pin "2") (pinfunction "A_2") (pintype "bidirectional"))
      (node (ref "IC5") (pin "1") (pinfunction "SW_1") (pintype "bidirectional"))
      (node (ref "L1") (pin "2") (pinfunction "2_2") (pintype "bidirectional"))
      (node (ref "R4") (pin "2") (pinfunction "2_2") (pintype "passive"))
    )
    (net (code "39") (name "Net-(IC1-VCAP_1)") (class "Default")
      (node (ref "C3") (pin "2") (pinfunction "2_2") (pintype "passive"))
      (node (ref "IC1") (pin "71") (pinfunction "VCAP_1_71") (pintype "bidirectional"))
    )
    (net (code "40") (name "Net-(IC1-VCAP_2)") (class "Default")
      (node (ref "C2") (pin "2") (pinfunction "2_2") (pintype "passive"))
      (node (ref "IC1") (pin "106") (pinfunction "VCAP_2_106") (pintype "bidirectional"))
    )
    (net (code "41") (name "Net-(LED1-PadA)") (class "Default")
      (node (ref "LED1") (pin "A") (pinfunction "A_A") (pintype "passive"))
      (node (ref "R11") (pin "1") (pinfunction "1_1") (pintype "passive"))
    )
    (net (code "42") (name "Net-(LED2-PadA)") (class "Default")
      (node (ref "LED2") (pin "A") (pinfunction "A_A") (pintype "passive"))
      (node (ref "R6") (pin "1") (pinfunction "1_1") (pintype "passive"))
    )
    (net (code "43") (name "Net-(LED3-PadA)") (class "Default")
      (node (ref "LED3") (pin "A") (pinfunction "A_A") (pintype "passive"))
      (node (ref "R9") (pin "1") (pinfunction "1_1") (pintype "passive"))
    )
    (net (code "44") (name "Net-(LED4-PadA)") (class "Default")
      (node (ref "LED4") (pin "A") (pinfunction "A_A") (pintype "passive"))
      (node (ref "R10") (pin "1") (pinfunction "1_1") (pintype "passive"))
    )
    (net (code "45") (name "Net-(Q1-S)") (class "Default")
      (node (ref "C17") (pin "2") (pinfunction "2_2") (pintype "passive"))
      (node (ref "Q1") (pin "2") (pinfunction "S_2") (pintype "bidirectional"))
      (node (ref "R25") (pin "2") (pinfunction "2_2") (pintype "passive"))
      (node (ref "R5") (pin "1") (pinfunction "1_1") (pintype "passive"))
    )
    (net (code "46") (name "Net-(Q2-S)") (class "Default")
      (node (ref "C9") (pin "2") (pinfunction "2_2") (pintype "passive"))
      (node (ref "Q2") (pin "2") (pinfunction "S_2") (pintype "bidirectional"))
      (node (ref "R12") (pin "2") (pinfunction "2_2") (pintype "passive"))
      (node (ref "R7") (pin "1") (pinfunction "1_1") (pintype "passive"))
    )
    (net (code "47") (name "Net-(Q3-S)") (class "Default")
      (node (ref "C7") (pin "2") (pinfunction "2_2") (pintype "passive"))
      (node (ref "Q3") (pin "2") (pinfunction "S_2") (pintype "bidirectional"))
      (node (ref "R14") (pin "2") (pinfunction "2_2") (pintype "passive"))
      (node (ref "R8") (pin "1") (pinfunction "1_1") (pintype "passive"))
    )
    (net (code "48") (name "Net-(Q4-D)") (class "Default")
      (node (ref "C5") (pin "1") (pinfunction "1_1") (pintype "passive"))
      (node (ref "L1") (pin "1") (pinfunction "1_1") (pintype "bidirectional"))
      (node (ref "Q4") (pin "3") (pinfunction "D_3") (pintype "bidirectional"))
    )
    (net (code "49") (name "Net-(Q5-D)") (class "Default")
      (node (ref "JP5") (pin "3") (pinfunction "3_3") (pintype "passive"))
      (node (ref "Q5") (pin "3") (pinfunction "D_3") (pintype "bidirectional"))
    )
    (net (code "50") (name "Net-(Q5-S)") (class "Default")
      (node (ref "C8") (pin "2") (pinfunction "2_2") (pintype "passive"))
      (node (ref "Q5") (pin "2") (pinfunction "S_2") (pintype "bidirectional"))
      (node (ref "R21") (pin "1") (pinfunction "1_1") (pintype "passive"))
      (node (ref "R22") (pin "2") (pinfunction "2_2") (pintype "passive"))
    )
    (net (code "51") (name "RCC_OSC32_IN") (class "Default")
      (node (ref "C18") (pin "2") (pinfunction "2_2") (pintype "passive"))
      (node (ref "CD-32KHZ") (pin "P$2") (pinfunction "C1_P$2") (pintype "bidirectional"))
      (node (ref "IC1") (pin "8") (pinfunction "PC14_8") (pintype "bidirectional"))
    )
    (net (code "52") (name "RCC_OSC32_OUT") (class "Default")
      (node (ref "C19") (pin "2") (pinfunction "2_2") (pintype "passive"))
      (node (ref "CD-32KHZ") (pin "P$1") (pinfunction "C0_P$1") (pintype "bidirectional"))
      (node (ref "IC1") (pin "9") (pinfunction "PC15_9") (pintype "bidirectional"))
    )
    (net (code "53") (name "RCC_OSC_IN") (class "Default")
      (node (ref "C20") (pin "2") (pinfunction "2_2") (pintype "passive"))
      (node (ref "CD_8MHZ") (pin "3") (pinfunction "C1_3") (pintype "bidirectional"))
      (node (ref "IC1") (pin "23") (pinfunction "PH0_23") (pintype "bidirectional"))
      (node (ref "R1") (pin "2") (pinfunction "2_2") (pintype "passive"))
    )
    (net (code "54") (name "RCC_OSC_OUT") (class "Default")
      (node (ref "C21") (pin "2") (pinfunction "2_2") (pintype "passive"))
      (node (ref "CD_8MHZ") (pin "1") (pinfunction "C0_1") (pintype "bidirectional"))
      (node (ref "IC1") (pin "24") (pinfunction "PH1_24") (pintype "bidirectional"))
      (node (ref "R1") (pin "1") (pinfunction "1_1") (pintype "passive"))
    )
    (net (code "55") (name "RD") (class "Default")
      (node (ref "IC1") (pin "20") (pinfunction "PF8_20") (pintype "bidirectional"))
      (node (ref "LCD") (pin "30") (pinfunction "30_30") (pintype "passive"))
    )
    (net (code "56") (name "RS") (class "Default")
      (node (ref "IC1") (pin "22") (pinfunction "PF10_22") (pintype "bidirectional"))
      (node (ref "LCD") (pin "34") (pinfunction "34_34") (pintype "passive"))
    )
    (net (code "57") (name "RST") (class "Default")
      (node (ref "IC1") (pin "50") (pinfunction "PF12_50") (pintype "bidirectional"))
      (node (ref "LCD") (pin "8") (pinfunction "8_8") (pintype "passive"))
    )
    (net (code "58") (name "SHUTDOWN") (class "Default")
      (node (ref "JP3") (pin "2") (pinfunction "2_2") (pintype "passive"))
      (node (ref "LDO") (pin "P$3") (pinfunction "EN_P$3") (pintype "bidirectional"))
      (node (ref "R16") (pin "2") (pinfunction "2_2") (pintype "passive"))
    )
    (net (code "59") (name "SPI1_MISO") (class "Default")
      (node (ref "IC1") (pin "42") (pinfunction "PA6_42") (pintype "bidirectional"))
      (node (ref "U1") (pin "A2") (pinfunction "MISO_A2") (pintype "bidirectional"))
    )
    (net (code "60") (name "SPI1_MOSI") (class "Default")
      (node (ref "IC1") (pin "43") (pinfunction "PA7_43") (pintype "bidirectional"))
      (node (ref "U1") (pin "A3") (pinfunction "MOSI_A3") (pintype "bidirectional"))
    )
    (net (code "61") (name "SPI1_NSS") (class "Default")
      (node (ref "IC1") (pin "40") (pinfunction "PA4_40") (pintype "bidirectional"))
      (node (ref "U1") (pin "A5") (pinfunction "NSS_A5") (pintype "bidirectional"))
    )
    (net (code "62") (name "SPI1_SCK") (class "Default")
      (node (ref "IC1") (pin "41") (pinfunction "PA5_41") (pintype "bidirectional"))
      (node (ref "U1") (pin "A4") (pinfunction "SCK_A4") (pintype "bidirectional"))
    )
    (net (code "63") (name "SPI2_MISO") (class "Default")
      (node (ref "IC1") (pin "28") (pinfunction "PC2_28") (pintype "bidirectional"))
      (node (ref "R19") (pin "1") (pinfunction "1_1") (pintype "passive"))
      (node (ref "SPI2") (pin "4") (pinfunction "4_4") (pintype "passive"))
    )
    (net (code "64") (name "SPI2_MOSI") (class "Default")
      (node (ref "IC1") (pin "27") (pinfunction "PC1_27") (pintype "bidirectional"))
      (node (ref "SPI2") (pin "6") (pinfunction "6_6") (pintype "passive"))
    )
    (net (code "65") (name "SPI2_NSS") (class "Default")
      (node (ref "IC1") (pin "73") (pinfunction "PB12_73") (pintype "bidirectional"))
      (node (ref "SPI2") (pin "5") (pinfunction "5_5") (pintype "passive"))
    )
    (net (code "66") (name "SPI2_SCK") (class "Default")
      (node (ref "IC1") (pin "74") (pinfunction "PB13_74") (pintype "bidirectional"))
      (node (ref "R20") (pin "1") (pinfunction "1_1") (pintype "passive"))
      (node (ref "SPI2") (pin "3") (pinfunction "3_3") (pintype "passive"))
    )
    (net (code "67") (name "SUP_EN") (class "Default")
      (node (ref "JP6") (pin "2") (pinfunction "2_2") (pintype "passive"))
      (node (ref "Q4") (pin "1") (pinfunction "G_1") (pintype "bidirectional"))
      (node (ref "R23") (pin "2") (pinfunction "2_2") (pintype "passive"))
    )
    (net (code "68") (name "SWDCLK") (class "Default")
      (node (ref "IC1") (pin "109") (pinfunction "PA14_109") (pintype "bidirectional"))
      (node (ref "JP1") (pin "4") (pinfunction "4_4") (pintype "bidirectional"))
    )
    (net (code "69") (name "SWDIO") (class "Default")
      (node (ref "IC1") (pin "105") (pinfunction "PA13_105") (pintype "bidirectional"))
      (node (ref "JP1") (pin "2") (pinfunction "2_2") (pintype "bidirectional"))
    )
    (net (code "70") (name "TCLK") (class "Default")
      (node (ref "IC1") (pin "2") (pinfunction "PE3_2") (pintype "bidirectional"))
      (node (ref "LCD") (pin "23") (pinfunction "23_23") (pintype "passive"))
    )
    (net (code "71") (name "TCS") (class "Default")
      (node (ref "IC1") (pin "1") (pinfunction "PE2_1") (pintype "bidirectional"))
      (node (ref "LCD") (pin "21") (pinfunction "21_21") (pintype "passive"))
    )
    (net (code "72") (name "TDIN") (class "Default")
      (node (ref "IC1") (pin "141") (pinfunction "PE0_141") (pintype "bidirectional"))
      (node (ref "LCD") (pin "19") (pinfunction "19_19") (pintype "passive"))
    )
    (net (code "73") (name "TDO") (class "Default")
      (node (ref "IC1") (pin "142") (pinfunction "PE1_142") (pintype "bidirectional"))
      (node (ref "LCD") (pin "15") (pinfunction "15_15") (pintype "passive"))
    )
    (net (code "74") (name "TIRQ") (class "Default")
      (node (ref "IC1") (pin "3") (pinfunction "PE4_3") (pintype "bidirectional"))
      (node (ref "LCD") (pin "13") (pinfunction "13_13") (pintype "passive"))
    )
    (net (code "75") (name "US1_INT") (class "Default")
      (node (ref "IC1") (pin "134") (pinfunction "PB4_134") (pintype "bidirectional"))
      (node (ref "IC1") (pin "135") (pinfunction "PB5_135") (pintype "bidirectional"))
      (node (ref "US1") (pin "5") (pinfunction "5_5") (pintype "passive"))
    )
    (net (code "76") (name "US2_INT") (class "Default")
      (node (ref "US2") (pin "5") (pinfunction "5_5") (pintype "passive"))
    )
    (net (code "77") (name "USART1_RX") (class "Default")
      (node (ref "IC1") (pin "76") (pinfunction "PB15_76") (pintype "bidirectional"))
      (node (ref "UART1") (pin "4") (pinfunction "4_4") (pintype "passive"))
    )
    (net (code "78") (name "USART1_TX") (class "Default")
      (node (ref "IC1") (pin "75") (pinfunction "PB14_75") (pintype "bidirectional"))
      (node (ref "UART1") (pin "3") (pinfunction "3_3") (pintype "passive"))
    )
    (net (code "79") (name "USART2_CTS") (class "Default")
      (node (ref "IC1") (pin "34") (pinfunction "PA0_34") (pintype "bidirectional"))
      (node (ref "UART2") (pin "5") (pinfunction "5_5") (pintype "passive"))
    )
    (net (code "80") (name "USART2_RTS") (class "Default")
      (node (ref "IC1") (pin "35") (pinfunction "PA1_35") (pintype "bidirectional"))
      (node (ref "UART2") (pin "6") (pinfunction "6_6") (pintype "passive"))
    )
    (net (code "81") (name "USART2_RX") (class "Default")
      (node (ref "IC1") (pin "37") (pinfunction "PA3_37") (pintype "bidirectional"))
      (node (ref "UART2") (pin "4") (pinfunction "4_4") (pintype "passive"))
    )
    (net (code "82") (name "USART2_TX") (class "Default")
      (node (ref "IC1") (pin "36") (pinfunction "PA2_36") (pintype "bidirectional"))
      (node (ref "UART2") (pin "3") (pinfunction "3_3") (pintype "passive"))
    )
    (net (code "83") (name "USB_OTG_FS_DM") (class "Default")
      (node (ref "IC1") (pin "103") (pinfunction "PA11_103") (pintype "bidirectional"))
      (node (ref "USB") (pin "2") (pinfunction "D-_2") (pintype "bidirectional"))
    )
    (net (code "84") (name "USB_OTG_FS_DP") (class "Default")
      (node (ref "IC1") (pin "104") (pinfunction "PA12_104") (pintype "bidirectional"))
      (node (ref "USB") (pin "3") (pinfunction "D+_3") (pintype "bidirectional"))
    )
    (net (code "85") (name "USB_OTG_FS_ID") (class "Default")
      (node (ref "IC1") (pin "102") (pinfunction "PA10_102") (pintype "bidirectional"))
      (node (ref "USB") (pin "4") (pinfunction "ID_4") (pintype "bidirectional"))
    )
    (net (code "86") (name "USB_OTG_FS_VBUS") (class "Default")
      (node (ref "IC1") (pin "101") (pinfunction "PA9_101") (pintype "bidirectional"))
      (node (ref "USB") (pin "1") (pinfunction "VBUS_1") (pintype "bidirectional"))
    )
    (net (code "87") (name "VBAT") (class "Default")
      (node (ref "BAT0") (pin "1") (pinfunction "1_1") (pintype "passive"))
      (node (ref "BAT1") (pin "1") (pinfunction "1_1") (pintype "passive"))
      (node (ref "C14") (pin "1") (pinfunction "1_1") (pintype "passive"))
      (node (ref "IC1") (pin "6") (pinfunction "VBAT_6") (pintype "bidirectional"))
      (node (ref "JP3") (pin "1") (pinfunction "1_1") (pintype "passive"))
      (node (ref "LDO") (pin "P$1") (pinfunction "IN_P$1") (pintype "bidirectional"))
      (node (ref "Q4") (pin "2") (pinfunction "S_2") (pintype "bidirectional"))
      (node (ref "R23") (pin "1") (pinfunction "1_1") (pintype "passive"))
      (node (ref "TVS1") (pin "2") (pinfunction "2_2") (pintype "passive"))
    )
    (net (code "88") (name "VCC_US1") (class "Default")
      (node (ref "Q2") (pin "3") (pinfunction "D_3") (pintype "bidirectional"))
      (node (ref "US1") (pin "1") (pinfunction "1_1") (pintype "passive"))
    )
    (net (code "89") (name "VCC_US2") (class "Default")
      (node (ref "Q1") (pin "3") (pinfunction "D_3") (pintype "bidirectional"))
      (node (ref "US2") (pin "1") (pinfunction "1_1") (pintype "passive"))
    )
    (net (code "90") (name "WR") (class "Default")
      (node (ref "IC1") (pin "21") (pinfunction "PF9_21") (pintype "bidirectional"))
      (node (ref "LCD") (pin "32") (pinfunction "32_32") (pintype "passive"))
    )
    (net (code "91") (name "unconnected-(IC1-BOOT0-Pad138)") (class "Default")
      (node (ref "IC1") (pin "138") (pinfunction "BOOT0_138") (pintype "bidirectional"))
    )
    (net (code "92") (name "unconnected-(IC1-PA15-Pad110)") (class "Default")
      (node (ref "IC1") (pin "110") (pinfunction "PA15_110") (pintype "bidirectional"))
    )
    (net (code "93") (name "unconnected-(IC1-PB3-Pad133)") (class "Default")
      (node (ref "IC1") (pin "133") (pinfunction "PB3_133") (pintype "bidirectional"))
    )
    (net (code "94") (name "unconnected-(IC1-PB6-Pad136)") (class "Default")
      (node (ref "IC1") (pin "136") (pinfunction "PB6_136") (pintype "bidirectional"))
    )
    (net (code "95") (name "unconnected-(IC1-PB9-Pad140)") (class "Default")
      (node (ref "IC1") (pin "140") (pinfunction "PB9_140") (pintype "bidirectional"))
    )
    (net (code "96") (name "unconnected-(IC1-PC0-Pad26)") (class "Default")
      (node (ref "IC1") (pin "26") (pinfunction "PC0_26") (pintype "bidirectional"))
    )
    (net (code "97") (name "unconnected-(IC1-PC3-Pad29)") (class "Default")
      (node (ref "IC1") (pin "29") (pinfunction "PC3_29") (pintype "bidirectional"))
    )
    (net (code "98") (name "unconnected-(IC1-PC10-Pad111)") (class "Default")
      (node (ref "IC1") (pin "111") (pinfunction "PC10_111") (pintype "bidirectional"))
    )
    (net (code "99") (name "unconnected-(IC1-PC11-Pad112)") (class "Default")
      (node (ref "IC1") (pin "112") (pinfunction "PC11_112") (pintype "bidirectional"))
    )
    (net (code "100") (name "unconnected-(IC1-PC12-Pad113)") (class "Default")
      (node (ref "IC1") (pin "113") (pinfunction "PC12_113") (pintype "bidirectional"))
    )
    (net (code "101") (name "unconnected-(IC1-PC13-Pad7)") (class "Default")
      (node (ref "IC1") (pin "7") (pinfunction "PC13_7") (pintype "bidirectional"))
    )
    (net (code "102") (name "unconnected-(IC1-PD0-Pad114)") (class "Default")
      (node (ref "IC1") (pin "114") (pinfunction "PD0_114") (pintype "bidirectional"))
    )
    (net (code "103") (name "unconnected-(IC1-PD1-Pad115)") (class "Default")
      (node (ref "IC1") (pin "115") (pinfunction "PD1_115") (pintype "bidirectional"))
    )
    (net (code "104") (name "unconnected-(IC1-PD2-Pad116)") (class "Default")
      (node (ref "IC1") (pin "116") (pinfunction "PD2_116") (pintype "bidirectional"))
    )
    (net (code "105") (name "unconnected-(IC1-PD3-Pad117)") (class "Default")
      (node (ref "IC1") (pin "117") (pinfunction "PD3_117") (pintype "bidirectional"))
    )
    (net (code "106") (name "unconnected-(IC1-PD4-Pad118)") (class "Default")
      (node (ref "IC1") (pin "118") (pinfunction "PD4_118") (pintype "bidirectional"))
    )
    (net (code "107") (name "unconnected-(IC1-PD5-Pad119)") (class "Default")
      (node (ref "IC1") (pin "119") (pinfunction "PD5_119") (pintype "bidirectional"))
    )
    (net (code "108") (name "unconnected-(IC1-PD6-Pad122)") (class "Default")
      (node (ref "IC1") (pin "122") (pinfunction "PD6_122") (pintype "bidirectional"))
    )
    (net (code "109") (name "unconnected-(IC1-PD7-Pad123)") (class "Default")
      (node (ref "IC1") (pin "123") (pinfunction "PD7_123") (pintype "bidirectional"))
    )
    (net (code "110") (name "unconnected-(IC1-PD9-Pad78)") (class "Default")
      (node (ref "IC1") (pin "78") (pinfunction "PD9_78") (pintype "bidirectional"))
    )
    (net (code "111") (name "unconnected-(IC1-PD10-Pad79)") (class "Default")
      (node (ref "IC1") (pin "79") (pinfunction "PD10_79") (pintype "bidirectional"))
    )
    (net (code "112") (name "unconnected-(IC1-PD11-Pad80)") (class "Default")
      (node (ref "IC1") (pin "80") (pinfunction "PD11_80") (pintype "bidirectional"))
    )
    (net (code "113") (name "unconnected-(IC1-PD12-Pad81)") (class "Default")
      (node (ref "IC1") (pin "81") (pinfunction "PD12_81") (pintype "bidirectional"))
    )
    (net (code "114") (name "unconnected-(IC1-PD13-Pad82)") (class "Default")
      (node (ref "IC1") (pin "82") (pinfunction "PD13_82") (pintype "bidirectional"))
    )
    (net (code "115") (name "unconnected-(IC1-PD14-Pad85)") (class "Default")
      (node (ref "IC1") (pin "85") (pinfunction "PD14_85") (pintype "bidirectional"))
    )
    (net (code "116") (name "unconnected-(IC1-PD15-Pad86)") (class "Default")
      (node (ref "IC1") (pin "86") (pinfunction "PD15_86") (pintype "bidirectional"))
    )
    (net (code "117") (name "unconnected-(IC1-PDR_ON-Pad143)") (class "Default")
      (node (ref "IC1") (pin "143") (pinfunction "PDR_ON_143") (pintype "bidirectional"))
    )
    (net (code "118") (name "unconnected-(IC1-PE5-Pad4)") (class "Default")
      (node (ref "IC1") (pin "4") (pinfunction "PE5_4") (pintype "bidirectional"))
    )
    (net (code "119") (name "unconnected-(IC1-PE6-Pad5)") (class "Default")
      (node (ref "IC1") (pin "5") (pinfunction "PE6_5") (pintype "bidirectional"))
    )
    (net (code "120") (name "unconnected-(IC1-PE7-Pad58)") (class "Default")
      (node (ref "IC1") (pin "58") (pinfunction "PE7_58") (pintype "bidirectional"))
    )
    (net (code "121") (name "unconnected-(IC1-PE8-Pad59)") (class "Default")
      (node (ref "IC1") (pin "59") (pinfunction "PE8_59") (pintype "bidirectional"))
    )
    (net (code "122") (name "unconnected-(IC1-PE9-Pad60)") (class "Default")
      (node (ref "IC1") (pin "60") (pinfunction "PE9_60") (pintype "bidirectional"))
    )
    (net (code "123") (name "unconnected-(IC1-PE10-Pad63)") (class "Default")
      (node (ref "IC1") (pin "63") (pinfunction "PE10_63") (pintype "bidirectional"))
    )
    (net (code "124") (name "unconnected-(IC1-PE11-Pad64)") (class "Default")
      (node (ref "IC1") (pin "64") (pinfunction "PE11_64") (pintype "bidirectional"))
    )
    (net (code "125") (name "unconnected-(IC1-PE12-Pad65)") (class "Default")
      (node (ref "IC1") (pin "65") (pinfunction "PE12_65") (pintype "bidirectional"))
    )
    (net (code "126") (name "unconnected-(IC1-PE13-Pad66)") (class "Default")
      (node (ref "IC1") (pin "66") (pinfunction "PE13_66") (pintype "bidirectional"))
    )
    (net (code "127") (name "unconnected-(IC1-PE14-Pad67)") (class "Default")
      (node (ref "IC1") (pin "67") (pinfunction "PE14_67") (pintype "bidirectional"))
    )
    (net (code "128") (name "unconnected-(IC1-PE15-Pad68)") (class "Default")
      (node (ref "IC1") (pin "68") (pinfunction "PE15_68") (pintype "bidirectional"))
    )
    (net (code "129") (name "unconnected-(IC1-PF13-Pad53)") (class "Default")
      (node (ref "IC1") (pin "53") (pinfunction "PF13_53") (pintype "bidirectional"))
    )
    (net (code "130") (name "unconnected-(IC1-PG0-Pad56)") (class "Default")
      (node (ref "IC1") (pin "56") (pinfunction "PG0_56") (pintype "bidirectional"))
    )
    (net (code "131") (name "unconnected-(IC1-PG1-Pad57)") (class "Default")
      (node (ref "IC1") (pin "57") (pinfunction "PG1_57") (pintype "bidirectional"))
    )
    (net (code "132") (name "unconnected-(IC1-PG2-Pad87)") (class "Default")
      (node (ref "IC1") (pin "87") (pinfunction "PG2_87") (pintype "bidirectional"))
    )
    (net (code "133") (name "unconnected-(IC1-PG3-Pad88)") (class "Default")
      (node (ref "IC1") (pin "88") (pinfunction "PG3_88") (pintype "bidirectional"))
    )
    (net (code "134") (name "unconnected-(IC1-PG4-Pad89)") (class "Default")
      (node (ref "IC1") (pin "89") (pinfunction "PG4_89") (pintype "bidirectional"))
    )
    (net (code "135") (name "unconnected-(IC1-PG5-Pad90)") (class "Default")
      (node (ref "IC1") (pin "90") (pinfunction "PG5_90") (pintype "bidirectional"))
    )
    (net (code "136") (name "unconnected-(IC1-PG6-Pad91)") (class "Default")
      (node (ref "IC1") (pin "91") (pinfunction "PG6_91") (pintype "bidirectional"))
    )
    (net (code "137") (name "unconnected-(IC1-PG7-Pad92)") (class "Default")
      (node (ref "IC1") (pin "92") (pinfunction "PG7_92") (pintype "bidirectional"))
    )
    (net (code "138") (name "unconnected-(IC1-PG8-Pad93)") (class "Default")
      (node (ref "IC1") (pin "93") (pinfunction "PG8_93") (pintype "bidirectional"))
    )
    (net (code "139") (name "unconnected-(IC1-PG9-Pad124)") (class "Default")
      (node (ref "IC1") (pin "124") (pinfunction "PG9_124") (pintype "bidirectional"))
    )
    (net (code "140") (name "unconnected-(IC1-PG10-Pad125)") (class "Default")
      (node (ref "IC1") (pin "125") (pinfunction "PG10_125") (pintype "bidirectional"))
    )
    (net (code "141") (name "unconnected-(IC1-PG11-Pad126)") (class "Default")
      (node (ref "IC1") (pin "126") (pinfunction "PG11_126") (pintype "bidirectional"))
    )
    (net (code "142") (name "unconnected-(IC1-PG12-Pad127)") (class "Default")
      (node (ref "IC1") (pin "127") (pinfunction "PG12_127") (pintype "bidirectional"))
    )
    (net (code "143") (name "unconnected-(IC1-PG13-Pad128)") (class "Default")
      (node (ref "IC1") (pin "128") (pinfunction "PG13_128") (pintype "bidirectional"))
    )
    (net (code "144") (name "unconnected-(IC1-PG14-Pad129)") (class "Default")
      (node (ref "IC1") (pin "129") (pinfunction "PG14_129") (pintype "bidirectional"))
    )
    (net (code "145") (name "unconnected-(IC1-PG15-Pad132)") (class "Default")
      (node (ref "IC1") (pin "132") (pinfunction "PG15_132") (pintype "bidirectional"))
    )
    (net (code "146") (name "unconnected-(IC1-VSS_9-Pad130)") (class "Default")
      (node (ref "IC1") (pin "130") (pinfunction "VSS_9_130") (pintype "bidirectional"))
    )
    (net (code "147") (name "unconnected-(IC5-NC_1-Pad3)") (class "Default")
      (node (ref "IC5") (pin "3") (pinfunction "NC_1_3") (pintype "bidirectional"))
    )
    (net (code "148") (name "unconnected-(IC5-NC_2-Pad5)") (class "Default")
      (node (ref "IC5") (pin "5") (pinfunction "NC_2_5") (pintype "bidirectional"))
    )
    (net (code "149") (name "unconnected-(JP1-Pad6)") (class "Default")
      (node (ref "JP1") (pin "6") (pinfunction "6_6") (pintype "bidirectional"))
    )
    (net (code "150") (name "unconnected-(JP1-Pad8)") (class "Default")
      (node (ref "JP1") (pin "8") (pinfunction "8_8") (pintype "bidirectional"))
    )
    (net (code "151") (name "unconnected-(LCD-Pad1)") (class "Default")
      (node (ref "LCD") (pin "1") (pinfunction "1_1") (pintype "passive"))
    )
    (net (code "152") (name "unconnected-(LCD-Pad2)") (class "Default")
      (node (ref "LCD") (pin "2") (pinfunction "2_2") (pintype "passive"))
    )
    (net (code "153") (name "unconnected-(LCD-Pad3)") (class "Default")
      (node (ref "LCD") (pin "3") (pinfunction "3_3") (pintype "passive"))
    )
    (net (code "154") (name "unconnected-(LCD-Pad5)") (class "Default")
      (node (ref "LCD") (pin "5") (pinfunction "5_5") (pintype "passive"))
    )
    (net (code "155") (name "unconnected-(LCD-Pad7)") (class "Default")
      (node (ref "LCD") (pin "7") (pinfunction "7_7") (pintype "passive"))
    )
    (net (code "156") (name "unconnected-(LCD-Pad9)") (class "Default")
      (node (ref "LCD") (pin "9") (pinfunction "9_9") (pintype "passive"))
    )
    (net (code "157") (name "unconnected-(LCD-Pad10)") (class "Default")
      (node (ref "LCD") (pin "10") (pinfunction "10_10") (pintype "passive"))
    )
    (net (code "158") (name "unconnected-(LCD-Pad11)") (class "Default")
      (node (ref "LCD") (pin "11") (pinfunction "11_11") (pintype "passive"))
    )
    (net (code "159") (name "unconnected-(LCD-Pad14)") (class "Default")
      (node (ref "LCD") (pin "14") (pinfunction "14_14") (pintype "passive"))
    )
    (net (code "160") (name "unconnected-(LCD-Pad16)") (class "Default")
      (node (ref "LCD") (pin "16") (pinfunction "16_16") (pintype "passive"))
    )
    (net (code "161") (name "unconnected-(LCD-Pad17)") (class "Default")
      (node (ref "LCD") (pin "17") (pinfunction "17_17") (pintype "passive"))
    )
    (net (code "162") (name "unconnected-(LCD-Pad18)") (class "Default")
      (node (ref "LCD") (pin "18") (pinfunction "18_18") (pintype "passive"))
    )
    (net (code "163") (name "unconnected-(LCD-Pad20)") (class "Default")
      (node (ref "LCD") (pin "20") (pinfunction "20_20") (pintype "passive"))
    )
    (net (code "164") (name "unconnected-(LCD-Pad22)") (class "Default")
      (node (ref "LCD") (pin "22") (pinfunction "22_22") (pintype "passive"))
    )
    (net (code "165") (name "unconnected-(LCD-Pad24)") (class "Default")
      (node (ref "LCD") (pin "24") (pinfunction "24_24") (pintype "passive"))
    )
    (net (code "166") (name "unconnected-(LCD-Pad26)") (class "Default")
      (node (ref "LCD") (pin "26") (pinfunction "26_26") (pintype "passive"))
    )
    (net (code "167") (name "unconnected-(LCD-Pad28)") (class "Default")
      (node (ref "LCD") (pin "28") (pinfunction "28_28") (pintype "passive"))
    )
    (net (code "168") (name "unconnected-(LCD-Pad36)") (class "Default")
      (node (ref "LCD") (pin "36") (pinfunction "36_36") (pintype "passive"))
    )
    (net (code "169") (name "unconnected-(LDO-N{slash}C-PadP$4)") (class "Default")
      (node (ref "LDO") (pin "P$4") (pinfunction "N/C_P$4") (pintype "no_connect"))
    )
    (net (code "170") (name "unconnected-(R3-Pad1)") (class "Default")
      (node (ref "R3") (pin "1") (pinfunction "1_1") (pintype "passive"))
    )
    (net (code "171") (name "unconnected-(US1-Pad6)") (class "Default")
      (node (ref "US1") (pin "6") (pinfunction "6_6") (pintype "passive"))
    )
    (net (code "172") (name "unconnected-(US2-Pad6)") (class "Default")
      (node (ref "US2") (pin "6") (pinfunction "6_6") (pintype "passive"))
    )
  )
)
